# minireg-xcl247.net
KiCad netlist of a schematic drawn in Altium Designer
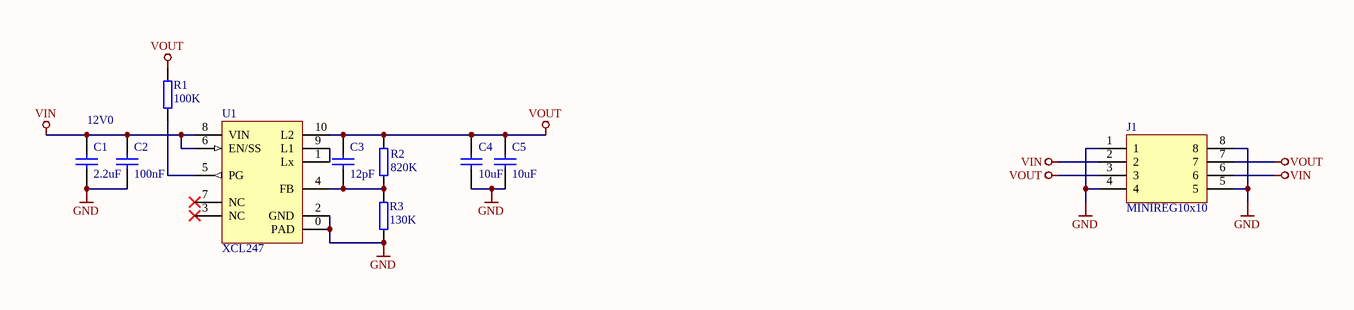
[diagram p0: minireg-xcl247.SchDoc]

(export (version "E")
  (design (tool "Eeschema 10.0.6"))
  (components
    (comp (ref "C1")
      (value "2.2uF")
      (footprint "CAP0603")
      (description "CAP SM 0603 X5R 2.2uF")
      (fields (field (name "PART NUMBER") "CAP-SM-0603-X5R-2.2uF") (field (name "MANUFACTURER") "GENERIC"))
      (libsource (lib "electronpowered") (part "CAP"))
    )
    (comp (ref "C2")
      (value "100nF")
      (footprint "CAP0603")
      (description "CAP SM 0603 X7R 100nF")
      (fields (field (name "PART NUMBER") "CAP-SM-0603-X7R-100nF") (field (name "MANUFACTURER") "GENERIC"))
      (libsource (lib "electronpowered") (part "CAP"))
    )
    (comp (ref "C3")
      (value "12pF")
      (footprint "CAP0603")
      (description "CAP SM 0603 NP0 12pF")
      (fields (field (name "PART NUMBER") "CAP-SM-0603-NP0-12pF") (field (name "MANUFACTURER") "GENERIC"))
      (libsource (lib "electronpowered") (part "CAP"))
    )
    (comp (ref "C4")
      (value "10uF")
      (footprint "CAP0603")
      (description "CAP SM 0603 X5R 10uF")
      (fields (field (name "PART NUMBER") "CAP-SM-0603-X5R-10uF") (field (name "MANUFACTURER") "GENERIC"))
      (libsource (lib "electronpowered") (part "CAP"))
    )
    (comp (ref "C5")
      (value "10uF")
      (footprint "CAP0603")
      (description "CAP SM 0603 X5R 10uF")
      (fields (field (name "PART NUMBER") "CAP-SM-0603-X5R-10uF") (field (name "MANUFACTURER") "GENERIC"))
      (libsource (lib "electronpowered") (part "CAP"))
    )
    (comp (ref "J1")
      (value "MINIREG10x10")
      (footprint "MINIREG8_10x10R")
      (libsource (lib "minireg") (part "MINIREG10x10"))
    )
    (comp (ref "R1")
      (value "100K")
      (footprint "RES0603")
      (description "RES SM 0603 100K")
      (fields (field (name "PART NUMBER") "RES-SM-0603-100K") (field (name "MANUFACTURER") "GENERIC"))
      (libsource (lib "electronpowered") (part "RES"))
    )
    (comp (ref "R2")
      (value "820K")
      (footprint "RES0603")
      (description "RES SM 0603 820K")
      (fields (field (name "PART NUMBER") "RES-SM-0603-820K") (field (name "MANUFACTURER") "GENERIC"))
      (libsource (lib "electronpowered") (part "RES"))
    )
    (comp (ref "R3")
      (value "130K")
      (footprint "RES0603")
      (description "RES SM 0603 130K")
      (fields (field (name "PART NUMBER") "RES-SM-0603-130K") (field (name "MANUFACTURER") "GENERIC"))
      (libsource (lib "electronpowered") (part "RES"))
    )
    (comp (ref "U1")
      (value "XCL247")
      (footprint "TOREX DFN3030-10B")
      (libsource (lib "minireg") (part "XCL247"))
    )
  )
  (nets
    (net (code "1") (name "GND") (class "Default")
      (node (ref "C1") (pin "1") (pinfunction "1_1") (pintype "passive"))
      (node (ref "C2") (pin "1") (pinfunction "1_1") (pintype "passive"))
      (node (ref "C4") (pin "1") (pinfunction "1_1") (pintype "passive"))
      (node (ref "C5") (pin "1") (pinfunction "1_1") (pintype "passive"))
      (node (ref "J1") (pin "1") (pinfunction "1_1") (pintype "power_in"))
      (node (ref "J1") (pin "4") (pinfunction "4_4") (pintype "power_in"))
      (node (ref "J1") (pin "5") (pinfunction "5_5") (pintype "power_in"))
      (node (ref "J1") (pin "8") (pinfunction "8_8") (pintype "power_in"))
      (node (ref "R3") (pin "1") (pinfunction "1_1") (pintype "passive"))
      (node (ref "U1") (pin "0") (pinfunction "PAD_0") (pintype "power_in"))
      (node (ref "U1") (pin "2") (pinfunction "GND_2") (pintype "power_in"))
    )
    (net (code "2") (name "Net-(U1-FB)") (class "Default")
      (node (ref "C3") (pin "1") (pinfunction "1_1") (pintype "passive"))
      (node (ref "R2") (pin "1") (pinfunction "1_1") (pintype "passive"))
      (node (ref "R3") (pin "2") (pinfunction "2_2") (pintype "passive"))
      (node (ref "U1") (pin "4") (pinfunction "FB_4") (pintype "power_in"))
    )
    (net (code "3") (name "Net-(U1-L1)") (class "Default")
      (node (ref "U1") (pin "1") (pinfunction "Lx_1") (pintype "power_in"))
      (node (ref "U1") (pin "9") (pinfunction "L1_9") (pintype "power_in"))
    )
    (net (code "4") (name "Net-(U1-PG)") (class "Default")
      (node (ref "R1") (pin "1") (pinfunction "1_1") (pintype "passive"))
      (node (ref "U1") (pin "5") (pinfunction "PG_5") (pintype "output"))
    )
    (net (code "5") (name "VIN") (class "Default")
      (node (ref "C1") (pin "2") (pinfunction "2_2") (pintype "passive"))
      (node (ref "C2") (pin "2") (pinfunction "2_2") (pintype "passive"))
      (node (ref "J1") (pin "2") (pinfunction "2_2") (pintype "power_in"))
      (node (ref "J1") (pin "6") (pinfunction "6_6") (pintype "power_in"))
      (node (ref "U1") (pin "6") (pinfunction "EN/SS_6") (pintype "input"))
      (node (ref "U1") (pin "8") (pinfunction "VIN_8") (pintype "power_in"))
    )
    (net (code "6") (name "VOUT") (class "Default")
      (node (ref "C3") (pin "2") (pinfunction "2_2") (pintype "passive"))
      (node (ref "C4") (pin "2") (pinfunction "2_2") (pintype "passive"))
      (node (ref "C5") (pin "2") (pinfunction "2_2") (pintype "passive"))
      (node (ref "J1") (pin "3") (pinfunction "3_3") (pintype "power_in"))
      (node (ref "J1") (pin "7") (pinfunction "7_7") (pintype "power_in"))
      (node (ref "R1") (pin "2") (pinfunction "2_2") (pintype "passive"))
      (node (ref "R2") (pin "2") (pinfunction "2_2") (pintype "passive"))
      (node (ref "U1") (pin "10") (pinfunction "L2_10") (pintype "power_in"))
    )
    (net (code "7") (name "unconnected-(U1-NC-Pad3)") (class "Default")
      (node (ref "U1") (pin "3") (pinfunction "NC_3") (pintype "power_in+no_connect"))
    )
    (net (code "8") (name "unconnected-(U1-NC-Pad7)") (class "Default")
      (node (ref "U1") (pin "7") (pinfunction "NC_7") (pintype "power_in+no_connect"))
    )
  )
)
